# BoardID.net
KiCad netlist of a schematic drawn in Altium Designer
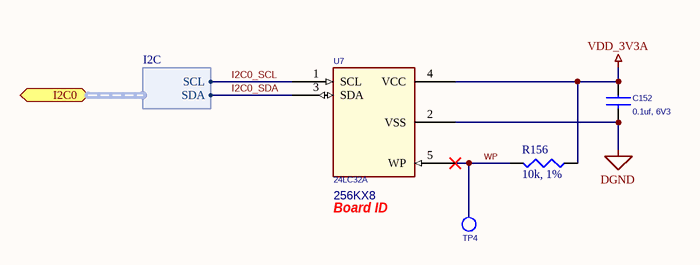
[diagram p0: BoardID.SchDoc]

(export (version "E")
  (design (tool "Eeschema 10.0.6"))
  (components
    (comp (ref "C152")
      (value "0.1uf, 6V3")
      (footprint "402")
      (description "CAP CER 0.1UF 6.3V 10% X5R 0402")
      (fields
        (field (name "MANUFACTURER") "TDK Corporation")
        (field (name "MANUFACTURER PART NUMBER") "C1005X5R0J104K050BA")
      )
      (libsource (lib "BEAGLEBONEBLACK_REV A5B") (part "CAP_0.1uF_X7R_16V_10% 0402"))
    )
    (comp (ref "R156")
      (value "10k, 1%")
      (footprint "402")
      (description "RES 10K OHM 1/16W 5% 0402 SMD")
      (fields
        (field (name "MANUFACTURER") "Rohm Semiconductor")
        (field (name "MANUFACTURER PART NUMBER") "MCR01MZPJ103")
      )
      (libsource (lib "BEAGLEBONEBLACK_REV A5B") (part "RES_10K_1/16W_1%_0402"))
    )
    (comp (ref "TP4")
      (value "TESTPT1")
      (footprint "tp1-8040")
      (libsource (lib "BEAGLEBONEBLACK_REV A5B") (part "TESTPT1"))
    )
    (comp (ref "U7")
      (value "24LC32A")
      (footprint "SOT23-5")
      (description "IC EEPROM 32KBIT 400KHZ SOT23-5")
      (fields
        (field (name "MANUFACTURER") "Microchip Technology")
        (field (name "MANUFACTURER PART NUMBER") "24LC32AT-I/OT")
      )
      (libsource (lib "BEAGLEBONEBLACK_REV A5B") (part "24LC32A"))
    )
  )
  (nets
    (net (code "2") (name "/I2C0_SCL") (class "Default")
      (node (ref "U7") (pin "1") (pinfunction "SCL_1") (pintype "input"))
    )
    (net (code "3") (name "/I2C0_SDA") (class "Default")
      (node (ref "U7") (pin "3") (pinfunction "SDA_3") (pintype "bidirectional"))
    )
    (net (code "4") (name "/WP") (class "Default")
      (node (ref "R156") (pin "2") (pinfunction "2_2") (pintype "passive"))
      (node (ref "TP4") (pin "1") (pinfunction "TP_1") (pintype "passive"))
      (node (ref "U7") (pin "5") (pinfunction "WP_5") (pintype "input"))
    )
    (net (code "6") (name "DGND") (class "Default")
      (node (ref "C152") (pin "2") (pinfunction "2_2") (pintype "passive"))
      (node (ref "U7") (pin "2") (pinfunction "VSS_2") (pintype "power_in"))
    )
    (net (code "7") (name "VDD_3V3A") (class "Default")
      (node (ref "C152") (pin "1") (pinfunction "1_1") (pintype "passive"))
      (node (ref "R156") (pin "1") (pinfunction "1_1") (pintype "passive"))
      (node (ref "U7") (pin "4") (pinfunction "VCC_4") (pintype "power_in"))
    )
  )
)
